# CH32L103F8U6-R0.net
KiCad netlist of a schematic drawn in Altium Designer
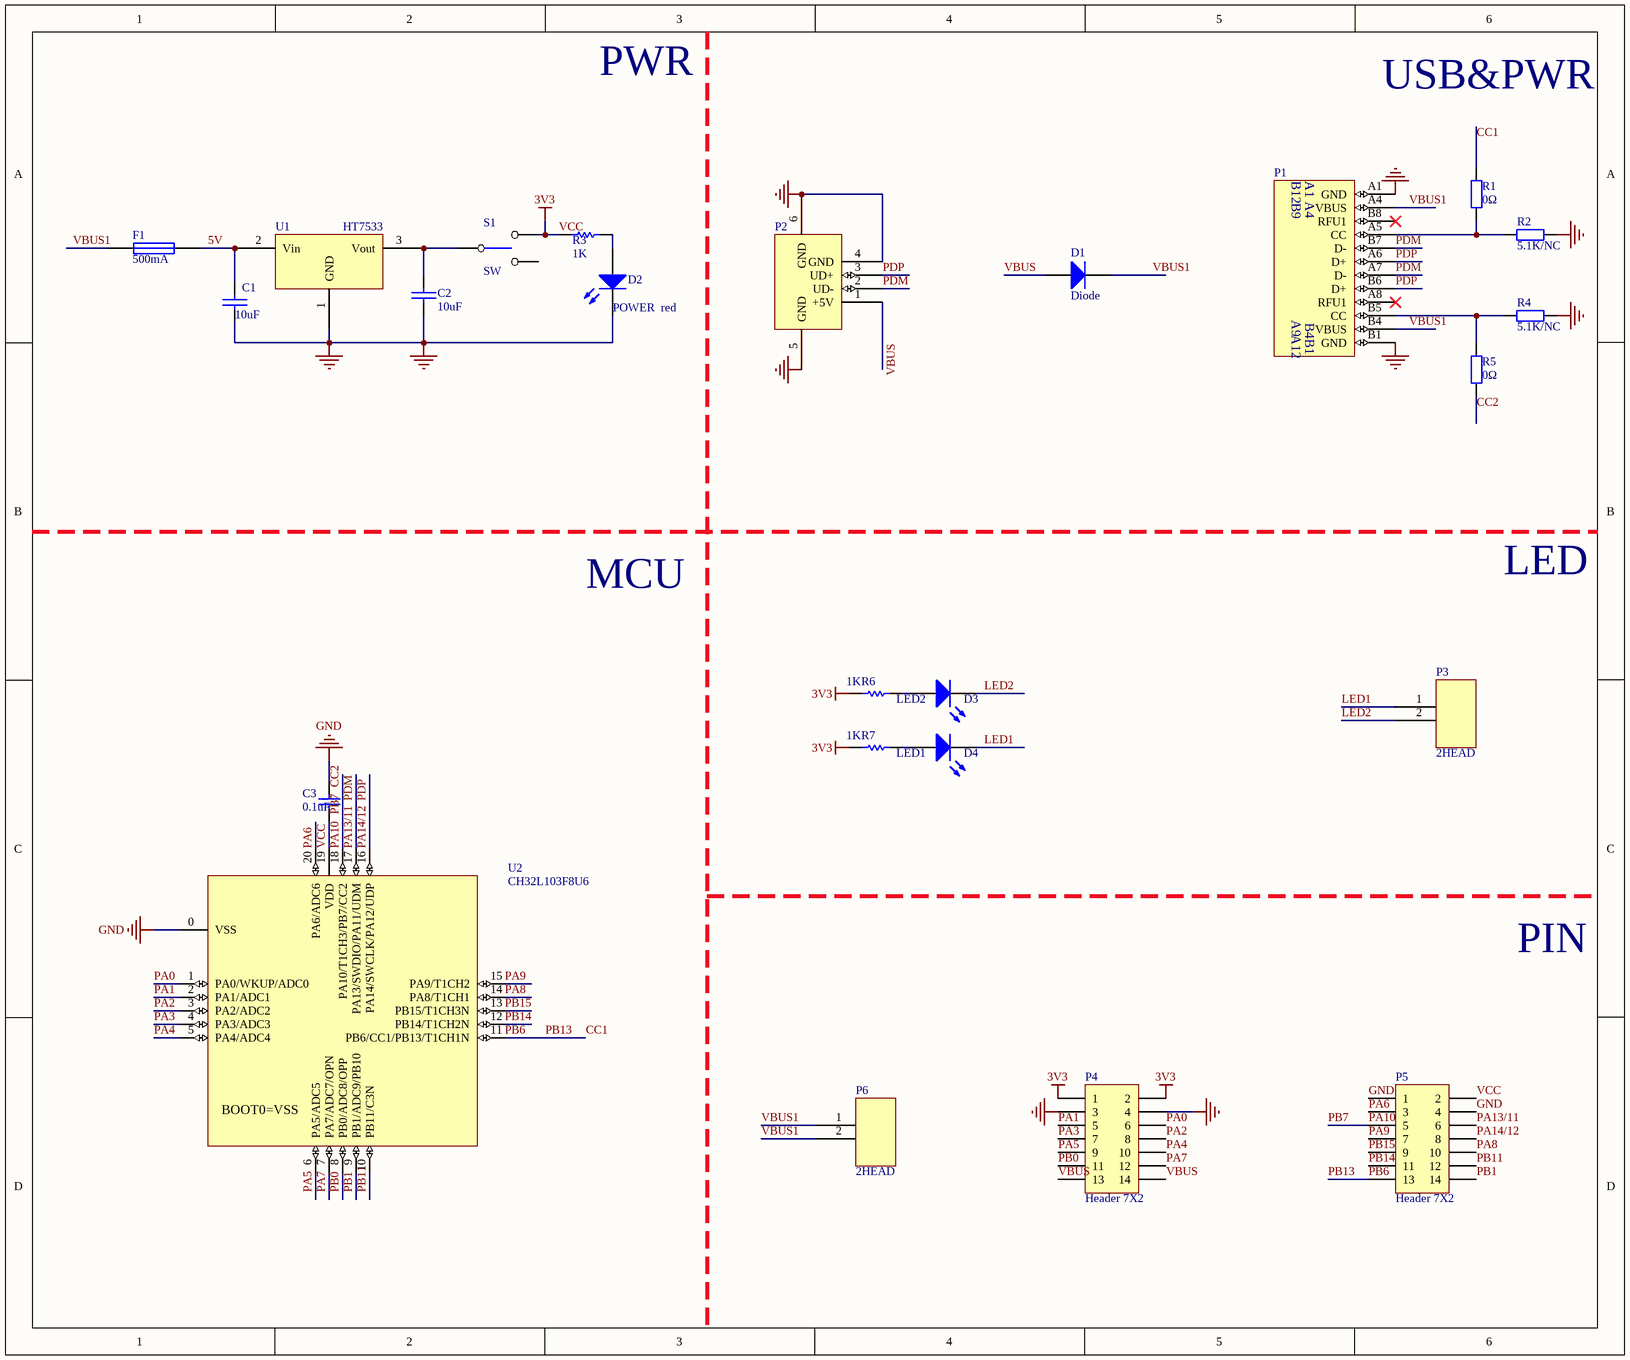
[diagram p0: CH32L103F8U6-R0.SchDoc]

(export (version "E")
  (design (tool "Eeschema 10.0.6"))
  (components
    (comp (ref "C1")
      (value "10uF")
      (footprint "0603_C")
      (description "Capacitor")
      (libsource (lib "*") (part "CAP"))
    )
    (comp (ref "C2")
      (value "10uF")
      (footprint "0603_C")
      (description "Capacitor")
      (libsource (lib "*") (part "CAP"))
    )
    (comp (ref "C3")
      (value "0.1uF")
      (footprint "0603_C")
      (description "Capacitor")
      (fields (field (name "PUBLISHER") "Altium Limited"))
      (libsource (lib "*") (part "Cap"))
    )
    (comp (ref "D1")
      (value "Diode")
      (footprint "SOD-123")
      (description "Default Diode")
      (fields (field (name "PUBLISHER") "Altium Limited"))
      (libsource (lib "Miscellaneous Devices") (part "Diode"))
    )
    (comp (ref "D2")
      (value "POWER  red")
      (footprint "0603+")
      (description "Typical INFRARED GaAs LED")
      (fields (field (name "PUBLISHER") "Altium Limited"))
      (libsource (lib "*") (part "LED0"))
    )
    (comp (ref "D3")
      (value "LED2")
      (footprint "0603+")
      (description "Typical INFRARED GaAs LED")
      (fields (field (name "PUBLISHER") "Altium Limited"))
      (libsource (lib "*") (part "LED0"))
    )
    (comp (ref "D4")
      (value "LED1")
      (footprint "0603+")
      (description "Typical INFRARED GaAs LED")
      (fields (field (name "PUBLISHER") "Altium Limited"))
      (libsource (lib "*") (part "LED0"))
    )
    (comp (ref "F1")
      (value "500mA")
      (footprint "0603")
      (description "Fuse")
      (libsource (lib "*") (part "FUSE1"))
    )
    (comp (ref "P1")
      (value "TYPE-C")
      (footprint "TYPE-C-Receptacle-2.0")
      (libsource (lib "*") (part "TYPE-C1"))
    )
    (comp (ref "P2")
      (value "USB_A")
      (footprint "USBAF")
      (description "USB Port")
      (libsource (lib "*") (part "USB"))
    )
    (comp (ref "P3") (value "2HEAD") (footprint "SIP2-2.54mm") (libsource (lib "*") (part "2HEAD")))
    (comp (ref "P4")
      (value "Header 7X2")
      (footprint "IDC14-2.54mm")
      (description "Header, 7-Pin, Dual row")
      (fields (field (name "PUBLISHER") "Altium Limited"))
      (libsource (lib "Miscellaneous Connectors") (part "Header 7X2"))
    )
    (comp (ref "P5")
      (value "Header 7X2")
      (footprint "IDC14-2.54mm")
      (description "Header, 7-Pin, Dual row")
      (fields (field (name "PUBLISHER") "Altium Limited"))
      (libsource (lib "Miscellaneous Connectors") (part "Header 7X2"))
    )
    (comp (ref "P6") (value "2HEAD") (footprint "SIP2-2.54mm") (libsource (lib "*") (part "2HEAD")))
    (comp (ref "R1")
      (value "0Ω")
      (footprint "0603")
      (description "Resistor")
      (libsource (lib "Miscellaneous Devices") (part "Res2"))
    )
    (comp (ref "R2")
      (value "5.1K/NC")
      (footprint "0603")
      (description "Resistor")
      (libsource (lib "") (part "Res2_1"))
    )
    (comp (ref "R3")
      (value "1K")
      (footprint "0603")
      (description "Semiconductor Resistor")
      (libsource (lib "*") (part "Res Semi"))
    )
    (comp (ref "R4")
      (value "5.1K/NC")
      (footprint "0603")
      (description "Resistor")
      (libsource (lib "") (part "Res2_1"))
    )
    (comp (ref "R5")
      (value "0Ω")
      (footprint "0603")
      (description "Resistor")
      (libsource (lib "Miscellaneous Devices") (part "Res2"))
    )
    (comp (ref "R6")
      (value "1K")
      (footprint "0603")
      (description "Semiconductor Resistor")
      (libsource (lib "*") (part "Res Semi"))
    )
    (comp (ref "R7")
      (value "1K")
      (footprint "0603")
      (description "Semiconductor Resistor")
      (libsource (lib "*") (part "Res Semi"))
    )
    (comp (ref "S1") (value "SW") (footprint "SW1") (libsource (lib "*") (part "SW")))
    (comp (ref "U1")
      (value "HT7533")
      (footprint "SOT-89")
      (libsource (lib "wch_sch_others") (part "1117-3.3V"))
    )
    (comp (ref "U2")
      (value "CH32L103F8U6")
      (footprint "QFN20_3X3")
      (description "RISC-V LMD-MCU, 96MHz, USB, Type-C/PD-5K1, CAN, OPA, lower power, for motor")
      (libsource (lib "CHXXX") (part "CH32L103F8U6"))
    )
  )
  (nets
    (net (code "1") (name "/5V") (class "Default")
      (node (ref "C1") (pin "1") (pinfunction "1_1") (pintype "passive"))
      (node (ref "F1") (pin "2") (pinfunction "2_2") (pintype "passive"))
      (node (ref "U1") (pin "2") (pinfunction "Vin_2") (pintype "passive"))
    )
    (net (code "3") (name "/CC1") (class "Default")
      (node (ref "P5") (pin "13") (pinfunction "13_13") (pintype "passive"))
      (node (ref "R1") (pin "2") (pinfunction "2_2") (pintype "passive"))
      (node (ref "U2") (pin "11") (pinfunction "PB6/CC1/PB13/T1CH1N_11") (pintype "bidirectional"))
    )
    (net (code "4") (name "/CC2") (class "Default")
      (node (ref "P5") (pin "5") (pinfunction "5_5") (pintype "passive"))
      (node (ref "R5") (pin "1") (pinfunction "1_1") (pintype "passive"))
      (node (ref "U2") (pin "18") (pinfunction "PA10/T1CH3/PB7/CC2_18") (pintype "bidirectional"))
    )
    (net (code "5") (name "/LED1") (class "Default")
      (node (ref "D4") (pin "2") (pinfunction "K_2") (pintype "passive"))
      (node (ref "P3") (pin "1") (pintype "passive"))
    )
    (net (code "6") (name "/LED2") (class "Default")
      (node (ref "D3") (pin "2") (pinfunction "K_2") (pintype "passive"))
      (node (ref "P3") (pin "2") (pintype "passive"))
    )
    (net (code "7") (name "/PA0") (class "Default")
      (node (ref "P4") (pin "6") (pinfunction "6_6") (pintype "passive"))
      (node (ref "U2") (pin "1") (pinfunction "PA0/WKUP/ADC0_1") (pintype "bidirectional"))
    )
    (net (code "8") (name "/PA1") (class "Default")
      (node (ref "P4") (pin "5") (pinfunction "5_5") (pintype "passive"))
      (node (ref "U2") (pin "2") (pinfunction "PA1/ADC1_2") (pintype "bidirectional"))
    )
    (net (code "9") (name "/PA2") (class "Default")
      (node (ref "P4") (pin "8") (pinfunction "8_8") (pintype "passive"))
      (node (ref "U2") (pin "3") (pinfunction "PA2/ADC2_3") (pintype "bidirectional"))
    )
    (net (code "10") (name "/PA3") (class "Default")
      (node (ref "P4") (pin "7") (pinfunction "7_7") (pintype "passive"))
      (node (ref "U2") (pin "4") (pinfunction "PA3/ADC3_4") (pintype "bidirectional"))
    )
    (net (code "11") (name "/PA4") (class "Default")
      (node (ref "P4") (pin "10") (pinfunction "10_10") (pintype "passive"))
      (node (ref "U2") (pin "5") (pinfunction "PA4/ADC4_5") (pintype "bidirectional"))
    )
    (net (code "12") (name "/PA5") (class "Default")
      (node (ref "P4") (pin "9") (pinfunction "9_9") (pintype "passive"))
      (node (ref "U2") (pin "6") (pinfunction "PA5/ADC5_6") (pintype "bidirectional"))
    )
    (net (code "13") (name "/PA6") (class "Default")
      (node (ref "P5") (pin "3") (pinfunction "3_3") (pintype "passive"))
      (node (ref "U2") (pin "20") (pinfunction "PA6/ADC6_20") (pintype "bidirectional"))
    )
    (net (code "14") (name "/PA7") (class "Default")
      (node (ref "P4") (pin "12") (pinfunction "12_12") (pintype "passive"))
      (node (ref "U2") (pin "7") (pinfunction "PA7/ADC7/OPN_7") (pintype "bidirectional"))
    )
    (net (code "15") (name "/PA8") (class "Default")
      (node (ref "P5") (pin "10") (pinfunction "10_10") (pintype "passive"))
      (node (ref "U2") (pin "14") (pinfunction "PA8/T1CH1_14") (pintype "bidirectional"))
    )
    (net (code "16") (name "/PA9") (class "Default")
      (node (ref "P5") (pin "7") (pinfunction "7_7") (pintype "passive"))
      (node (ref "U2") (pin "15") (pinfunction "PA9/T1CH2_15") (pintype "bidirectional"))
    )
    (net (code "17") (name "/PA13{slash}11") (class "Default")
      (node (ref "P1") (pin "A7") (pinfunction "D-_A7") (pintype "bidirectional"))
      (node (ref "P1") (pin "B7") (pinfunction "D-_B7") (pintype "bidirectional"))
      (node (ref "P2") (pin "2") (pinfunction "UD-_2") (pintype "bidirectional"))
      (node (ref "P5") (pin "6") (pinfunction "6_6") (pintype "passive"))
      (node (ref "U2") (pin "17") (pinfunction "PA13/SWDIO/PA11/UDM_17") (pintype "bidirectional"))
    )
    (net (code "18") (name "/PA14{slash}12") (class "Default")
      (node (ref "P1") (pin "A6") (pinfunction "D+_A6") (pintype "bidirectional"))
      (node (ref "P1") (pin "B6") (pinfunction "D+_B6") (pintype "bidirectional"))
      (node (ref "P2") (pin "3") (pinfunction "UD+_3") (pintype "bidirectional"))
      (node (ref "P5") (pin "8") (pinfunction "8_8") (pintype "passive"))
      (node (ref "U2") (pin "16") (pinfunction "PA14/SWCLK/PA12/UDP_16") (pintype "bidirectional"))
    )
    (net (code "19") (name "/PB0") (class "Default")
      (node (ref "P4") (pin "11") (pinfunction "11_11") (pintype "passive"))
      (node (ref "U2") (pin "8") (pinfunction "PB0/ADC8/OPP_8") (pintype "bidirectional"))
    )
    (net (code "20") (name "/PB1") (class "Default")
      (node (ref "P5") (pin "14") (pinfunction "14_14") (pintype "passive"))
      (node (ref "U2") (pin "9") (pinfunction "PB1/ADC9/PB10_9") (pintype "bidirectional"))
    )
    (net (code "21") (name "/PB11") (class "Default")
      (node (ref "P5") (pin "12") (pinfunction "12_12") (pintype "passive"))
      (node (ref "U2") (pin "10") (pinfunction "PB11/C3N_10") (pintype "bidirectional"))
    )
    (net (code "22") (name "/PB14") (class "Default")
      (node (ref "P5") (pin "11") (pinfunction "11_11") (pintype "passive"))
      (node (ref "U2") (pin "12") (pinfunction "PB14/T1CH2N_12") (pintype "bidirectional"))
    )
    (net (code "23") (name "/PB15") (class "Default")
      (node (ref "P5") (pin "9") (pinfunction "9_9") (pintype "passive"))
      (node (ref "U2") (pin "13") (pinfunction "PB15/T1CH3N_13") (pintype "bidirectional"))
    )
    (net (code "24") (name "/VBUS") (class "Default")
      (node (ref "D1") (pin "1") (pinfunction "A_1") (pintype "passive"))
      (node (ref "P2") (pin "1") (pinfunction "+5V_1") (pintype "power_in"))
      (node (ref "P4") (pin "13") (pinfunction "13_13") (pintype "passive"))
      (node (ref "P4") (pin "14") (pinfunction "14_14") (pintype "passive"))
    )
    (net (code "25") (name "/VBUS1") (class "Default")
      (node (ref "D1") (pin "2") (pinfunction "K_2") (pintype "passive"))
      (node (ref "F1") (pin "1") (pinfunction "1_1") (pintype "passive"))
      (node (ref "P1") (pin "A4") (pinfunction "VBUS_A4") (pintype "bidirectional"))
      (node (ref "P1") (pin "B4") (pinfunction "VBUS_B4") (pintype "bidirectional"))
      (node (ref "P6") (pin "1") (pintype "passive"))
      (node (ref "P6") (pin "2") (pintype "passive"))
    )
    (net (code "26") (name "3V3") (class "Default")
      (node (ref "C3") (pin "1") (pinfunction "1_1") (pintype "passive"))
      (node (ref "P4") (pin "1") (pinfunction "1_1") (pintype "passive"))
      (node (ref "P4") (pin "2") (pinfunction "2_2") (pintype "passive"))
      (node (ref "P5") (pin "2") (pinfunction "2_2") (pintype "passive"))
      (node (ref "R3") (pin "2") (pinfunction "2_2") (pintype "passive"))
      (node (ref "R6") (pin "1") (pinfunction "1_1") (pintype "passive"))
      (node (ref "R7") (pin "1") (pinfunction "1_1") (pintype "passive"))
      (node (ref "S1") (pin "3") (pinfunction "3_3") (pintype "passive"))
      (node (ref "U2") (pin "19") (pinfunction "VDD_19") (pintype "power_in"))
    )
    (net (code "27") (name "GND") (class "Default")
      (node (ref "C1") (pin "2") (pinfunction "2_2") (pintype "passive"))
      (node (ref "C2") (pin "2") (pinfunction "2_2") (pintype "passive"))
      (node (ref "C3") (pin "2") (pinfunction "2_2") (pintype "passive"))
      (node (ref "D2") (pin "2") (pinfunction "K_2") (pintype "passive"))
      (node (ref "P1") (pin "A1") (pinfunction "GND_A1") (pintype "bidirectional"))
      (node (ref "P1") (pin "B1") (pinfunction "GND_B1") (pintype "bidirectional"))
      (node (ref "P2") (pin "4") (pinfunction "GND_4") (pintype "power_in"))
      (node (ref "P2") (pin "5") (pinfunction "GND_5") (pintype "power_in"))
      (node (ref "P2") (pin "6") (pinfunction "GND_6") (pintype "power_in"))
      (node (ref "P4") (pin "3") (pinfunction "3_3") (pintype "passive"))
      (node (ref "P4") (pin "4") (pinfunction "4_4") (pintype "passive"))
      (node (ref "P5") (pin "1") (pinfunction "1_1") (pintype "passive"))
      (node (ref "P5") (pin "4") (pinfunction "4_4") (pintype "passive"))
      (node (ref "R2") (pin "2") (pinfunction "2_2") (pintype "passive"))
      (node (ref "R4") (pin "2") (pinfunction "2_2") (pintype "passive"))
      (node (ref "U1") (pin "1") (pinfunction "GND_1") (pintype "passive"))
      (node (ref "U2") (pin "0") (pinfunction "VSS_0") (pintype "power_in"))
    )
    (net (code "28") (name "Net-(D2-A)") (class "Default")
      (node (ref "D2") (pin "1") (pinfunction "A_1") (pintype "passive"))
      (node (ref "R3") (pin "1") (pinfunction "1_1") (pintype "passive"))
    )
    (net (code "29") (name "Net-(D3-A)") (class "Default")
      (node (ref "D3") (pin "1") (pinfunction "A_1") (pintype "passive"))
      (node (ref "R6") (pin "2") (pinfunction "2_2") (pintype "passive"))
    )
    (net (code "30") (name "Net-(D4-A)") (class "Default")
      (node (ref "D4") (pin "1") (pinfunction "A_1") (pintype "passive"))
      (node (ref "R7") (pin "2") (pinfunction "2_2") (pintype "passive"))
    )
    (net (code "31") (name "Net-(P1-CC-PadA5)") (class "Default")
      (node (ref "P1") (pin "A5") (pinfunction "CC_A5") (pintype "bidirectional"))
      (node (ref "R1") (pin "1") (pinfunction "1_1") (pintype "passive"))
      (node (ref "R2") (pin "1") (pinfunction "1_1") (pintype "passive"))
    )
    (net (code "32") (name "Net-(P1-CC-PadB5)") (class "Default")
      (node (ref "P1") (pin "B5") (pinfunction "CC_B5") (pintype "bidirectional"))
      (node (ref "R4") (pin "1") (pinfunction "1_1") (pintype "passive"))
      (node (ref "R5") (pin "2") (pinfunction "2_2") (pintype "passive"))
    )
    (net (code "33") (name "Net-(U1-Vout)") (class "Default")
      (node (ref "C2") (pin "1") (pinfunction "1_1") (pintype "passive"))
      (node (ref "S1") (pin "1") (pinfunction "1_1") (pintype "passive"))
      (node (ref "U1") (pin "3") (pinfunction "Vout_3") (pintype "passive"))
    )
    (net (code "34") (name "unconnected-(P1-RFU1-PadA8)") (class "Default")
      (node (ref "P1") (pin "A8") (pinfunction "RFU1_A8") (pintype "bidirectional+no_connect"))
    )
    (net (code "35") (name "unconnected-(P1-RFU1-PadB8)") (class "Default")
      (node (ref "P1") (pin "B8") (pinfunction "RFU1_B8") (pintype "bidirectional+no_connect"))
    )
    (net (code "36") (name "unconnected-(S1-Pad2)") (class "Default")
      (node (ref "S1") (pin "2") (pinfunction "2_2") (pintype "passive"))
    )
  )
)
